# DRV8801.net
KiCad netlist of a schematic drawn in Altium Designer
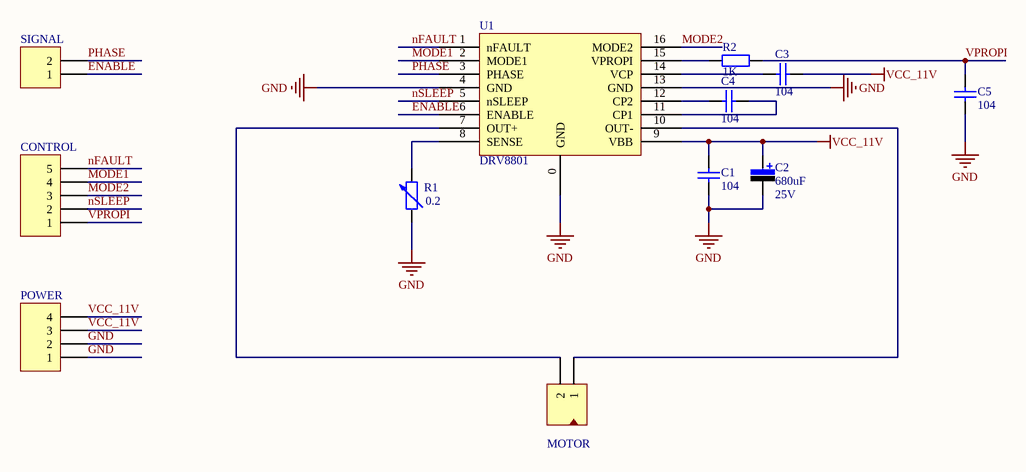
[diagram p0: DRV8801.SchDoc]

(export (version "E")
  (design (tool "Eeschema 10.0.6"))
  (components
    (comp (ref "C1")
      (value "104")
      (footprint "C-0603")
      (description "贴片瓷片电容")
      (fields (field (name "Comment") "Cap-S") (field (name "PUBLISHER") "Altium Limited"))
      (libsource (lib "Fszhang") (part "Cap-S"))
    )
    (comp (ref "C2")
      (value "680uF")
      (footprint "C-RB-5.0/10")
      (description "插件电解电容")
      (fields
        (field (name "VOL") "25V")
        (field (name "Comment") "Cap-Pol-ER")
        (field (name "PUBLISHER") "Altium Limited")
      )
      (libsource (lib "Fszhang") (part "Cap-Pol-ER"))
    )
    (comp (ref "C3")
      (value "104")
      (footprint "C-0603")
      (description "贴片瓷片电容")
      (fields (field (name "Comment") "Cap-S") (field (name "PUBLISHER") "Altium Limited"))
      (libsource (lib "Fszhang") (part "Cap-S"))
    )
    (comp (ref "C4")
      (value "104")
      (footprint "C-0603")
      (description "贴片瓷片电容")
      (fields (field (name "Comment") "Cap-S") (field (name "PUBLISHER") "Altium Limited"))
      (libsource (lib "Fszhang") (part "Cap-S"))
    )
    (comp (ref "C5")
      (value "104")
      (footprint "C-0603")
      (description "贴片瓷片电容")
      (fields (field (name "Comment") "Cap-S") (field (name "PUBLISHER") "Altium Limited"))
      (libsource (lib "Fszhang") (part "Cap-S"))
    )
    (comp (ref "CONTROL")
      (value "Header 5")
      (footprint "HDR1X5")
      (description "Header, 5-Pin")
      (fields (field (name "PUBLISHER") "Altium Limited"))
      (libsource (lib "Miscellaneous Connectors") (part "Header 5"))
    )
    (comp (ref "MOTOR")
      (value "Header 2")
      (footprint "HDR2X1-2.54")
      (description "接插件")
      (fields (field (name "PUBLISHER") "Altium Limited"))
      (libsource (lib "HDR_Fszhang") (part "Header 2"))
    )
    (comp (ref "POWER")
      (value "Header 4")
      (footprint "HDR1X4")
      (description "Header, 4-Pin")
      (fields (field (name "PUBLISHER") "Altium Limited"))
      (libsource (lib "Miscellaneous Connectors") (part "Header 4"))
    )
    (comp (ref "R1")
      (value "0.2")
      (footprint "AXIAL-0.6")
      (description "Variable Resistor")
      (fields (field (name "Comment") "Res Adj2") (field (name "PUBLISHER") "Altium Limited"))
      (libsource (lib "Miscellaneous Devices") (part "Res Adj2"))
    )
    (comp (ref "R2")
      (value "1K")
      (footprint "0603-1")
      (description "贴片电阻")
      (fields (field (name "Comment") "Res1") (field (name "PUBLISHER") "Altium Limited"))
      (libsource (lib "Fszhang") (part "Res1"))
    )
    (comp (ref "SIGNAL")
      (value "Header 2")
      (footprint "HDR1X2")
      (description "Header, 2-Pin")
      (fields (field (name "PUBLISHER") "Altium Limited"))
      (libsource (lib "Miscellaneous Connectors") (part "Header 2"))
    )
    (comp (ref "U1")
      (value "DRV8801")
      (footprint "HTSSOP16")
      (libsource (lib "HanZ_Library") (part "DRV8801"))
    )
  )
  (nets
    (net (code "1") (name "/ENABLE") (class "Default")
      (node (ref "SIGNAL") (pin "1") (pinfunction "1_1") (pintype "passive"))
      (node (ref "U1") (pin "6") (pinfunction "ENABLE_6") (pintype "passive"))
    )
    (net (code "2") (name "/MODE1") (class "Default")
      (node (ref "CONTROL") (pin "4") (pinfunction "4_4") (pintype "passive"))
      (node (ref "U1") (pin "2") (pinfunction "MODE1_2") (pintype "passive"))
    )
    (net (code "3") (name "/MODE2") (class "Default")
      (node (ref "CONTROL") (pin "3") (pinfunction "3_3") (pintype "passive"))
      (node (ref "U1") (pin "16") (pinfunction "MODE2_16") (pintype "passive"))
    )
    (net (code "4") (name "/PHASE") (class "Default")
      (node (ref "SIGNAL") (pin "2") (pinfunction "2_2") (pintype "passive"))
      (node (ref "U1") (pin "3") (pinfunction "PHASE_3") (pintype "passive"))
    )
    (net (code "5") (name "/VPROPI") (class "Default")
      (node (ref "C5") (pin "2") (pinfunction "2_2") (pintype "passive"))
      (node (ref "CONTROL") (pin "1") (pinfunction "1_1") (pintype "passive"))
      (node (ref "R2") (pin "2") (pinfunction "2_2") (pintype "passive"))
    )
    (net (code "6") (name "/nFAULT") (class "Default")
      (node (ref "CONTROL") (pin "5") (pinfunction "5_5") (pintype "passive"))
      (node (ref "U1") (pin "1") (pinfunction "nFAULT_1") (pintype "passive"))
    )
    (net (code "7") (name "/nSLEEP") (class "Default")
      (node (ref "CONTROL") (pin "2") (pinfunction "2_2") (pintype "passive"))
      (node (ref "U1") (pin "5") (pinfunction "nSLEEP_5") (pintype "passive"))
    )
    (net (code "8") (name "GND") (class "Default")
      (node (ref "C1") (pin "1") (pinfunction "1_1") (pintype "passive"))
      (node (ref "C2") (pin "2") (pinfunction "2_2") (pintype "passive"))
      (node (ref "C5") (pin "1") (pinfunction "1_1") (pintype "passive"))
      (node (ref "POWER") (pin "1") (pinfunction "1_1") (pintype "passive"))
      (node (ref "POWER") (pin "2") (pinfunction "2_2") (pintype "passive"))
      (node (ref "R1") (pin "1") (pinfunction "1_1") (pintype "passive"))
      (node (ref "U1") (pin "0") (pinfunction "GND_0") (pintype "passive"))
      (node (ref "U1") (pin "13") (pinfunction "GND_13") (pintype "passive"))
      (node (ref "U1") (pin "4") (pinfunction "GND_4") (pintype "passive"))
    )
    (net (code "9") (name "Net-(U1-CP1)") (class "Default")
      (node (ref "C4") (pin "1") (pinfunction "1_1") (pintype "passive"))
      (node (ref "U1") (pin "11") (pinfunction "CP1_11") (pintype "passive"))
    )
    (net (code "10") (name "Net-(U1-CP2)") (class "Default")
      (node (ref "C4") (pin "2") (pinfunction "2_2") (pintype "passive"))
      (node (ref "U1") (pin "12") (pinfunction "CP2_12") (pintype "passive"))
    )
    (net (code "11") (name "Net-(U1-OUT+)") (class "Default")
      (node (ref "MOTOR") (pin "2") (pinfunction "2_2") (pintype "passive"))
      (node (ref "U1") (pin "7") (pinfunction "OUT+_7") (pintype "passive"))
    )
    (net (code "12") (name "Net-(U1-OUT-)") (class "Default")
      (node (ref "MOTOR") (pin "1") (pinfunction "1_1") (pintype "passive"))
      (node (ref "U1") (pin "10") (pinfunction "OUT-_10") (pintype "passive"))
    )
    (net (code "13") (name "Net-(U1-SENSE)") (class "Default")
      (node (ref "R1") (pin "2") (pinfunction "2_2") (pintype "passive"))
      (node (ref "U1") (pin "8") (pinfunction "SENSE_8") (pintype "passive"))
    )
    (net (code "14") (name "Net-(U1-VCP)") (class "Default")
      (node (ref "C3") (pin "2") (pinfunction "2_2") (pintype "passive"))
      (node (ref "U1") (pin "14") (pinfunction "VCP_14") (pintype "passive"))
    )
    (net (code "15") (name "Net-(U1-VPROPI)") (class "Default")
      (node (ref "R2") (pin "1") (pinfunction "1_1") (pintype "passive"))
      (node (ref "U1") (pin "15") (pinfunction "VPROPI_15") (pintype "passive"))
    )
    (net (code "16") (name "VCC_11V") (class "Default")
      (node (ref "C1") (pin "2") (pinfunction "2_2") (pintype "passive"))
      (node (ref "C2") (pin "1") (pinfunction "1_1") (pintype "passive"))
      (node (ref "C3") (pin "1") (pinfunction "1_1") (pintype "passive"))
      (node (ref "POWER") (pin "3") (pinfunction "3_3") (pintype "passive"))
      (node (ref "POWER") (pin "4") (pinfunction "4_4") (pintype "passive"))
      (node (ref "U1") (pin "9") (pinfunction "VBB_9") (pintype "passive"))
    )
  )
)
